# sigmaDeltaComplete.net
KiCad netlist of a schematic drawn in Altium Designer
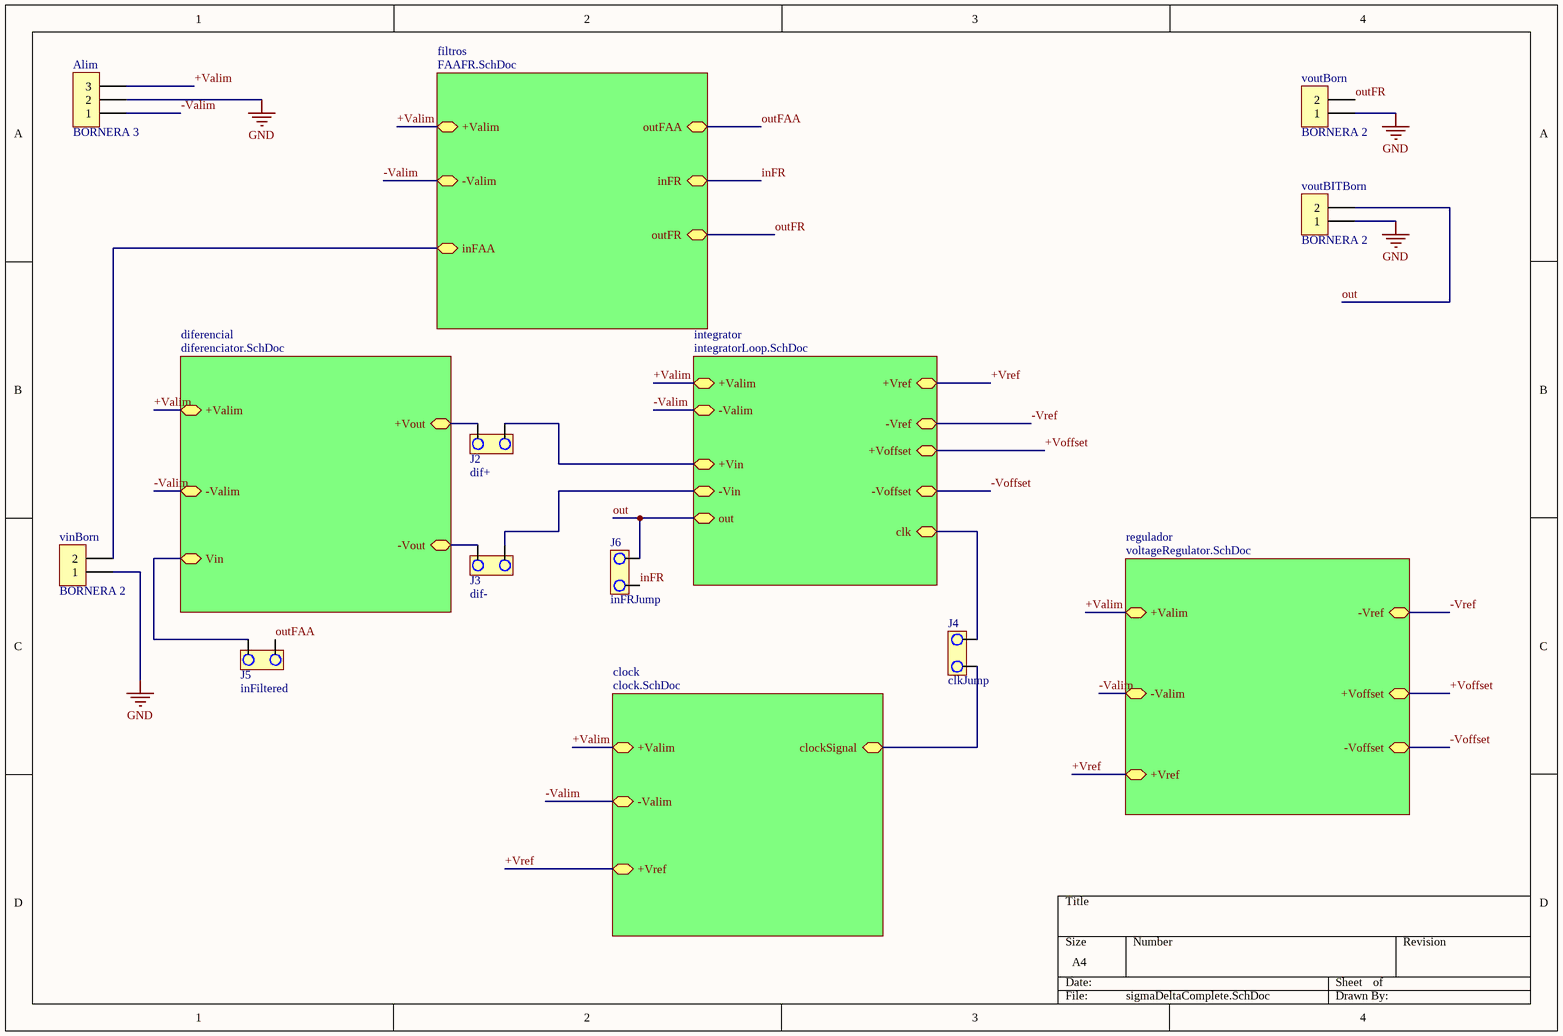
[diagram p0: sigmaDeltaComplete.SchDoc]

(export (version "E")
  (design (tool "Eeschema 10.0.6"))
  (components
    (comp (ref "Alim")
      (value "BORNERA 3")
      (footprint "BORNERA3")
      (libsource (lib "LIBEBAL") (part "BORNERA 3"))
    )
    (comp (ref "J2") (value "dif+") (footprint "JUMPER2") (libsource (lib "LIBEBAL") (part "JUMPER")))
    (comp (ref "J3") (value "dif-") (footprint "JUMPER2") (libsource (lib "LIBEBAL") (part "JUMPER")))
    (comp (ref "J4") (value "clkJump") (footprint "JUMPER2") (libsource (lib "") (part "JUMPER_1")))
    (comp (ref "J5") (value "inFiltered") (footprint "JUMPER2") (libsource (lib "LIBEBAL") (part "JUMPER")))
    (comp (ref "J6") (value "inFRJump") (footprint "JUMPER2") (libsource (lib "") (part "JUMPER_1")))
    (comp (ref "vinBorn")
      (value "BORNERA 2")
      (footprint "BORNERA2")
      (libsource (lib "LIBEBAL") (part "BORNERA 2"))
    )
    (comp (ref "voutBITBorn")
      (value "BORNERA 2")
      (footprint "BORNERA2")
      (libsource (lib "LIBEBAL") (part "BORNERA 2"))
    )
    (comp (ref "voutBorn")
      (value "BORNERA 2")
      (footprint "BORNERA2")
      (libsource (lib "LIBEBAL") (part "BORNERA 2"))
    )
  )
  (nets
    (net (code "1") (name "/+Valim") (class "Default")
      (node (ref "Alim") (pin "3") (pinfunction "3_3") (pintype "passive"))
    )
    (net (code "2") (name "/+Vin") (class "Default")
      (node (ref "J2") (pin "2") (pinfunction "2_2") (pintype "passive"))
    )
    (net (code "4") (name "/+Vout") (class "Default")
      (node (ref "J2") (pin "1") (pinfunction "1_1") (pintype "passive"))
    )
    (net (code "6") (name "/-Valim") (class "Default")
      (node (ref "Alim") (pin "1") (pinfunction "1_1") (pintype "passive"))
    )
    (net (code "7") (name "/-Vin") (class "Default")
      (node (ref "J3") (pin "2") (pinfunction "2_2") (pintype "passive"))
    )
    (net (code "9") (name "/-Vout") (class "Default")
      (node (ref "J3") (pin "1") (pinfunction "1_1") (pintype "passive"))
    )
    (net (code "11") (name "/Vin") (class "Default")
      (node (ref "J5") (pin "1") (pinfunction "1_1") (pintype "passive"))
    )
    (net (code "12") (name "/clk") (class "Default")
      (node (ref "J4") (pin "1") (pinfunction "1_1") (pintype "passive"))
    )
    (net (code "13") (name "/clockSignal") (class "Default")
      (node (ref "J4") (pin "2") (pinfunction "2_2") (pintype "passive"))
    )
    (net (code "14") (name "/inFAA") (class "Default")
      (node (ref "vinBorn") (pin "2") (pinfunction "2_2") (pintype "passive"))
    )
    (net (code "15") (name "/inFR") (class "Default")
      (node (ref "J6") (pin "2") (pinfunction "2_2") (pintype "passive"))
    )
    (net (code "16") (name "/out") (class "Default")
      (node (ref "J6") (pin "1") (pinfunction "1_1") (pintype "passive"))
      (node (ref "voutBITBorn") (pin "2") (pinfunction "2_2") (pintype "passive"))
    )
    (net (code "17") (name "/outFAA") (class "Default")
      (node (ref "J5") (pin "2") (pinfunction "2_2") (pintype "passive"))
    )
    (net (code "18") (name "/outFR") (class "Default")
      (node (ref "voutBorn") (pin "2") (pinfunction "2_2") (pintype "passive"))
    )
    (net (code "19") (name "GND") (class "Default")
      (node (ref "Alim") (pin "2") (pinfunction "2_2") (pintype "passive"))
      (node (ref "vinBorn") (pin "1") (pinfunction "1_1") (pintype "passive"))
      (node (ref "voutBITBorn") (pin "1") (pinfunction "1_1") (pintype "passive"))
      (node (ref "voutBorn") (pin "1") (pinfunction "1_1") (pintype "passive"))
    )
  )
)
